# main.net
KiCad netlist of a schematic drawn in Altium Designer
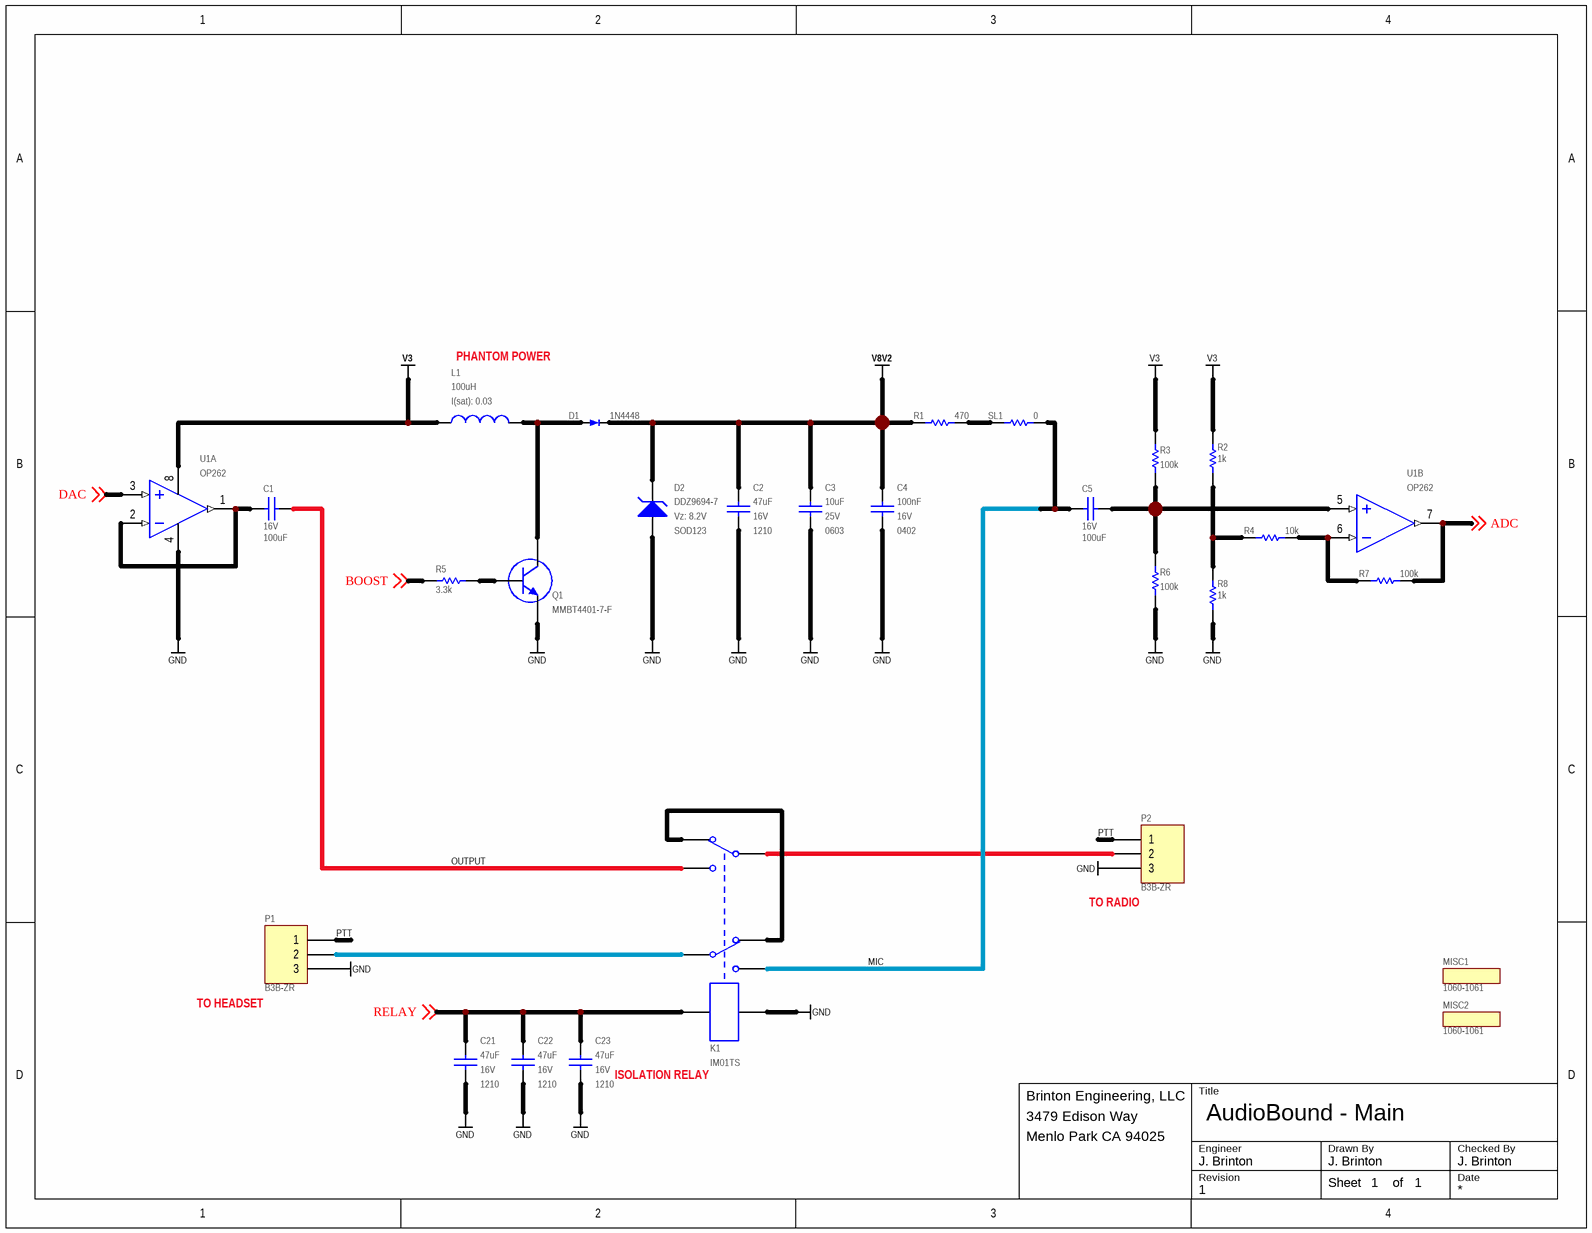
[diagram p0: main.SchDoc]

(export (version "E")
  (design (tool "Eeschema 10.0.6"))
  (components
    (comp (ref "C1")
      (value "100uF")
      (footprint "CAPC7563X300L40N")
      (description "Ceramic Capacitor 100uF ±20% 16V X7S 3025")
      (fields
        (field (name "MANUFACTURER") "TDK")
        (field (name "TOLERANCE") "±20%")
        (field (name "VOLTAGE") "16V")
      )
      (libsource (lib "") (part "CAP_1"))
    )
    (comp (ref "C2")
      (value "47uF")
      (footprint "generic:1210")
      (description "Ceramic Capacitor 47uF ±10% 16V X6S 1210")
      (fields
        (field (name "MANUFACTURER") "Murata")
        (field (name "TOLERANCE") "±10%")
        (field (name "VOLTAGE") "16V")
        (field (name "PACKAGE") "1210")
      )
      (libsource (lib "generic") (part "CAP"))
    )
    (comp (ref "C3")
      (value "10uF")
      (footprint "generic:0603")
      (description "Ceramic Capacitor 10uF ±20% 25V X5R 0603")
      (fields
        (field (name "MANUFACTURER") "Samsung")
        (field (name "VOLTAGE") "25V")
        (field (name "PACKAGE") "0603")
        (field (name "TOLERANCE") "±20%")
      )
      (libsource (lib "generic") (part "CAP 0603"))
    )
    (comp (ref "C4")
      (value "100nF")
      (footprint "generic:0402")
      (description "Ceramic Capacitor 100nF ±10% 16V X7R 0402")
      (fields
        (field (name "VOLTAGE") "16V")
        (field (name "MANUFACTURER") "Murata")
        (field (name "PACKAGE") "0402")
        (field (name "TOLERANCE") "±10%")
      )
      (libsource (lib "Graviton") (part "CAP 0402"))
    )
    (comp (ref "C5")
      (value "100uF")
      (footprint "CAPC7563X300L40N")
      (description "Ceramic Capacitor 100uF ±20% 16V X7S 3025")
      (fields
        (field (name "MANUFACTURER") "TDK")
        (field (name "TOLERANCE") "±20%")
        (field (name "VOLTAGE") "16V")
      )
      (libsource (lib "") (part "CAP_1"))
    )
    (comp (ref "C21")
      (value "47uF")
      (footprint "generic:1210")
      (description "Ceramic Capacitor 47uF ±10% 16V X6S 1210")
      (fields
        (field (name "MANUFACTURER") "Murata")
        (field (name "TOLERANCE") "±10%")
        (field (name "VOLTAGE") "16V")
        (field (name "PACKAGE") "1210")
      )
      (libsource (lib "generic") (part "CAP"))
    )
    (comp (ref "C22")
      (value "47uF")
      (footprint "generic:1210")
      (description "Ceramic Capacitor 47uF ±10% 16V X6S 1210")
      (fields
        (field (name "MANUFACTURER") "Murata")
        (field (name "TOLERANCE") "±10%")
        (field (name "VOLTAGE") "16V")
        (field (name "PACKAGE") "1210")
      )
      (libsource (lib "generic") (part "CAP"))
    )
    (comp (ref "C23")
      (value "47uF")
      (footprint "generic:1210")
      (description "Ceramic Capacitor 47uF ±10% 16V X6S 1210")
      (fields
        (field (name "MANUFACTURER") "Murata")
        (field (name "TOLERANCE") "±10%")
        (field (name "VOLTAGE") "16V")
        (field (name "PACKAGE") "1210")
      )
      (libsource (lib "generic") (part "CAP"))
    )
    (comp (ref "D1")
      (value "1N4448HWS-7-F")
      (footprint "diodes_inc:SOD323")
      (description "Schottky Diode 80V 250mA SOD323")
      (fields (field (name "MANUFACTURER") "Diodes, Inc.") (field (name "ALTERNATIVE P/N") "1N4448"))
      (libsource (lib "diodes_inc") (part "1N4448HWS-7-F"))
    )
    (comp (ref "D2")
      (value "DDZ9694-7")
      (footprint "generic:SOD123")
      (description "Zener Diode 8.2V 500mW SOD123")
      (fields
        (field (name "MANUFACTURER") "Diodes, Inc.")
        (field (name "VZ") "8.2V")
        (field (name "PACKAGE") "SOD123")
      )
      (libsource (lib "diodes_inc") (part "DDZ9694-7"))
    )
    (comp (ref "K1")
      (value "IM01TS")
      (footprint "IM01TS")
      (description "Dual-Pole Dual-Throw Relay")
      (fields (field (name "MANUFACTURER") "TE Connectivity"))
      (libsource (lib "te") (part "IM01TS"))
    )
    (comp (ref "L1")
      (value "100uH")
      (footprint "0805")
      (description "Inductor 100uH ±20% 140mA 0805")
      (fields
        (field (name "MANUFACTURER") "TDK")
        (field (name "TOLERANCE") "±20%")
        (field (name "I(SAT)") "0.03")
      )
      (libsource (lib "generic") (part "INDUCTOR"))
    )
    (comp (ref "MISC1")
      (value "1060-1061")
      (description "Strain Relief Bushing")
      (fields (field (name "MANUFACTURER") "Heyco"))
      (libsource (lib "harwin") (part "M50-1900005"))
    )
    (comp (ref "MISC2")
      (value "1060-1061")
      (description "Strain Relief Bushing")
      (fields (field (name "MANUFACTURER") "Heyco"))
      (libsource (lib "harwin") (part "M50-1900005"))
    )
    (comp (ref "P1")
      (value "B3B-ZR")
      (footprint "B3B-ZR")
      (description "Header, 3-Pin")
      (fields (field (name "MANUFACTURER") "JST"))
      (libsource (lib "") (part "Header 3_1"))
    )
    (comp (ref "P2")
      (value "B3B-ZR")
      (footprint "B3B-ZR")
      (description "Header, 3-Pin")
      (fields (field (name "MANUFACTURER") "JST"))
      (libsource (lib "Miscellaneous Connectors") (part "Header 3"))
    )
    (comp (ref "Q1")
      (value "MMBT4401-7-F")
      (footprint "generic:SOT23")
      (description "NPN Small Signal Transistor SMD SOT-23")
      (fields (field (name "MANUFACTURER P/N") "MMBT4401-7-F") (field (name "MANUFACTURER") "Diodes, Inc."))
      (libsource (lib "diodes_inc") (part "MMBT4401-7-F"))
    )
    (comp (ref "R1")
      (value "470")
      (footprint "RESC1005X40N")
      (description "Thick Film Resistor 470 ±1% 0.1W 50V 0402")
      (fields (field (name "MANUFACTURER") "Panasonic") (field (name "TOLERANCE") "±1%"))
      (libsource (lib "generic") (part "RES"))
    )
    (comp (ref "R2")
      (value "1k")
      (footprint "RESC1005X40N")
      (description "Thick Film Resistor 1k ±1% 0.1W 50V 0402")
      (fields (field (name "MANUFACTURER") "Panasonic") (field (name "TOLERANCE") "±1%"))
      (libsource (lib "generic") (part "RES"))
    )
    (comp (ref "R3")
      (value "100k")
      (footprint "RESC1005X40N")
      (description "Thick Film Resistor 100k ±1% 0.1W 50V 0402")
      (fields (field (name "MANUFACTURER") "Panasonic") (field (name "TOLERANCE") "±1%"))
      (libsource (lib "generic") (part "RES"))
    )
    (comp (ref "R4")
      (value "10k")
      (footprint "RESC1005X40N")
      (description "Thick Film Resistor 10k ±1% 0.1W 50V 0402")
      (fields (field (name "MANUFACTURER") "Panasonic") (field (name "TOLERANCE") "±1%"))
      (libsource (lib "generic") (part "RES"))
    )
    (comp (ref "R5")
      (value "3.3k")
      (footprint "RESC1005X40N")
      (description "Thick Film Resistor 3.3k ±1% 0.1W 50V 0402")
      (fields (field (name "MANUFACTURER") "Panasonic") (field (name "TOLERANCE") "±1%"))
      (libsource (lib "generic") (part "RES"))
    )
    (comp (ref "R6")
      (value "100k")
      (footprint "RESC1005X40N")
      (description "Thick Film Resistor 100k ±1% 0.1W 50V 0402")
      (fields (field (name "MANUFACTURER") "Panasonic") (field (name "TOLERANCE") "±1%"))
      (libsource (lib "generic") (part "RES"))
    )
    (comp (ref "R7")
      (value "100k")
      (footprint "RESC1005X40N")
      (description "Thick Film Resistor 100k ±1% 0.1W 50V 0402")
      (fields (field (name "MANUFACTURER") "Panasonic") (field (name "TOLERANCE") "±1%"))
      (libsource (lib "generic") (part "RES"))
    )
    (comp (ref "R8")
      (value "1k")
      (footprint "RESC1005X40N")
      (description "Thick Film Resistor 1k ±1% 0.1W 50V 0402")
      (fields (field (name "MANUFACTURER") "Panasonic") (field (name "TOLERANCE") "±1%"))
      (libsource (lib "generic") (part "RES"))
    )
    (comp (ref "SL1")
      (value "0")
      (footprint "SOLDERLINK0603X26N_BRIDGED")
      (description "Solder Link Bridged")
      (fields (field (name "Comment") "SOLDER_LINK_BRIDGED"))
      (libsource (lib "generic") (part "RES"))
    )
    (comp (ref "U1")
      (value "OP262")
      (footprint "TSSOP8")
      (description "Dual 15 MHz Rail-to-Rail Op Amp")
      (fields (field (name "MANUFACTURER") "Analog Devices"))
      (libsource (lib "analog_devices") (part "OP262"))
    )
  )
  (nets
    (net (code "1") (name "/MIC") (class "Default")
      (node (ref "C5") (pin "2") (pinfunction "2_2") (pintype "passive"))
      (node (ref "K1") (pin "4") (pinfunction "4_4") (pintype "passive"))
      (node (ref "SL1") (pin "2") (pinfunction "2_2") (pintype "passive"))
    )
    (net (code "2") (name "/OUTPUT") (class "Default")
      (node (ref "C1") (pin "1") (pinfunction "1_1") (pintype "passive"))
      (node (ref "K1") (pin "5") (pinfunction "5_5") (pintype "passive"))
    )
    (net (code "3") (name "/PTT") (class "Default")
      (node (ref "P1") (pin "1") (pinfunction "1_1") (pintype "passive"))
      (node (ref "P2") (pin "1") (pinfunction "1_1") (pintype "passive"))
    )
    (net (code "4") (name "ADC") (class "Default")
      (node (ref "R7") (pin "1") (pinfunction "1_1") (pintype "passive"))
      (node (ref "U1") (pin "7") (pinfunction "OUTB_7") (pintype "output"))
    )
    (net (code "5") (name "BOOST") (class "Default")
      (node (ref "R5") (pin "2") (pinfunction "2_2") (pintype "passive"))
    )
    (net (code "6") (name "DAC") (class "Default")
      (node (ref "U1") (pin "3") (pinfunction "INA+_3") (pintype "input"))
    )
    (net (code "7") (name "GND") (class "Default")
      (node (ref "C2") (pin "1") (pinfunction "1_1") (pintype "passive"))
      (node (ref "C21") (pin "1") (pinfunction "1_1") (pintype "passive"))
      (node (ref "C22") (pin "1") (pinfunction "1_1") (pintype "passive"))
      (node (ref "C23") (pin "1") (pinfunction "1_1") (pintype "passive"))
      (node (ref "C3") (pin "1") (pinfunction "1_1") (pintype "passive"))
      (node (ref "C4") (pin "2") (pinfunction "2_2") (pintype "passive"))
      (node (ref "D2") (pin "1") (pinfunction "A_1") (pintype "power_in"))
      (node (ref "K1") (pin "8") (pinfunction "8_8") (pintype "passive"))
      (node (ref "P1") (pin "3") (pinfunction "3_3") (pintype "passive"))
      (node (ref "P2") (pin "3") (pinfunction "3_3") (pintype "passive"))
      (node (ref "Q1") (pin "2") (pinfunction "E_2") (pintype "passive"))
      (node (ref "R6") (pin "1") (pinfunction "1_1") (pintype "passive"))
      (node (ref "R8") (pin "1") (pinfunction "1_1") (pintype "passive"))
      (node (ref "U1") (pin "4") (pinfunction "V-_4") (pintype "passive"))
    )
    (net (code "8") (name "Net-(K1-Pad2)") (class "Default")
      (node (ref "K1") (pin "2") (pinfunction "2_2") (pintype "passive"))
      (node (ref "K1") (pin "7") (pinfunction "7_7") (pintype "passive"))
    )
    (net (code "9") (name "Net-(K1-Pad3)") (class "Default")
      (node (ref "K1") (pin "3") (pinfunction "3_3") (pintype "passive"))
      (node (ref "P1") (pin "2") (pinfunction "2_2") (pintype "passive"))
    )
    (net (code "10") (name "Net-(K1-Pad6)") (class "Default")
      (node (ref "K1") (pin "6") (pinfunction "6_6") (pintype "passive"))
      (node (ref "P2") (pin "2") (pinfunction "2_2") (pintype "passive"))
    )
    (net (code "11") (name "Net-(Q1-B)") (class "Default")
      (node (ref "Q1") (pin "1") (pinfunction "B_1") (pintype "passive"))
      (node (ref "R5") (pin "1") (pinfunction "1_1") (pintype "passive"))
    )
    (net (code "12") (name "Net-(Q1-C)") (class "Default")
      (node (ref "D1") (pin "A") (pinfunction "A_A") (pintype "passive"))
      (node (ref "L1") (pin "2") (pinfunction "2_2") (pintype "passive"))
      (node (ref "Q1") (pin "3") (pinfunction "C_3") (pintype "passive"))
    )
    (net (code "13") (name "Net-(R1-Pad1)") (class "Default")
      (node (ref "R1") (pin "1") (pinfunction "1_1") (pintype "passive"))
      (node (ref "SL1") (pin "1") (pinfunction "1_1") (pintype "passive"))
    )
    (net (code "14") (name "Net-(R2-Pad1)") (class "Default")
      (node (ref "R2") (pin "1") (pinfunction "1_1") (pintype "passive"))
      (node (ref "R4") (pin "2") (pinfunction "2_2") (pintype "passive"))
      (node (ref "R8") (pin "2") (pinfunction "2_2") (pintype "passive"))
    )
    (net (code "15") (name "Net-(U1A-INA-)") (class "Default")
      (node (ref "C1") (pin "2") (pinfunction "2_2") (pintype "passive"))
      (node (ref "U1") (pin "1") (pinfunction "OUTA_1") (pintype "output"))
      (node (ref "U1") (pin "2") (pinfunction "INA-_2") (pintype "input"))
    )
    (net (code "16") (name "Net-(U1B-INB+)") (class "Default")
      (node (ref "C5") (pin "1") (pinfunction "1_1") (pintype "passive"))
      (node (ref "R3") (pin "1") (pinfunction "1_1") (pintype "passive"))
      (node (ref "R6") (pin "2") (pinfunction "2_2") (pintype "passive"))
      (node (ref "U1") (pin "5") (pinfunction "INB+_5") (pintype "input"))
    )
    (net (code "17") (name "Net-(U1B-INB-)") (class "Default")
      (node (ref "R4") (pin "1") (pinfunction "1_1") (pintype "passive"))
      (node (ref "R7") (pin "2") (pinfunction "2_2") (pintype "passive"))
      (node (ref "U1") (pin "6") (pinfunction "INB-_6") (pintype "input"))
    )
    (net (code "18") (name "RELAY") (class "Default")
      (node (ref "C21") (pin "2") (pinfunction "2_2") (pintype "passive"))
      (node (ref "C22") (pin "2") (pinfunction "2_2") (pintype "passive"))
      (node (ref "C23") (pin "2") (pinfunction "2_2") (pintype "passive"))
      (node (ref "K1") (pin "1") (pinfunction "1_1") (pintype "passive"))
    )
    (net (code "19") (name "V3") (class "Default")
      (node (ref "L1") (pin "1") (pinfunction "1_1") (pintype "passive"))
      (node (ref "R2") (pin "2") (pinfunction "2_2") (pintype "passive"))
      (node (ref "R3") (pin "2") (pinfunction "2_2") (pintype "passive"))
      (node (ref "U1") (pin "8") (pinfunction "V+_8") (pintype "passive"))
    )
    (net (code "20") (name "V8V2") (class "Default")
      (node (ref "C2") (pin "2") (pinfunction "2_2") (pintype "passive"))
      (node (ref "C3") (pin "2") (pinfunction "2_2") (pintype "passive"))
      (node (ref "C4") (pin "1") (pinfunction "1_1") (pintype "passive"))
      (node (ref "D1") (pin "K") (pinfunction "K_K") (pintype "passive"))
      (node (ref "D2") (pin "2") (pinfunction "C_2") (pintype "passive"))
      (node (ref "R1") (pin "2") (pinfunction "2_2") (pintype "passive"))
    )
  )
)
